# gismoviv1.net
KiCad netlist of a schematic drawn in EAGLE
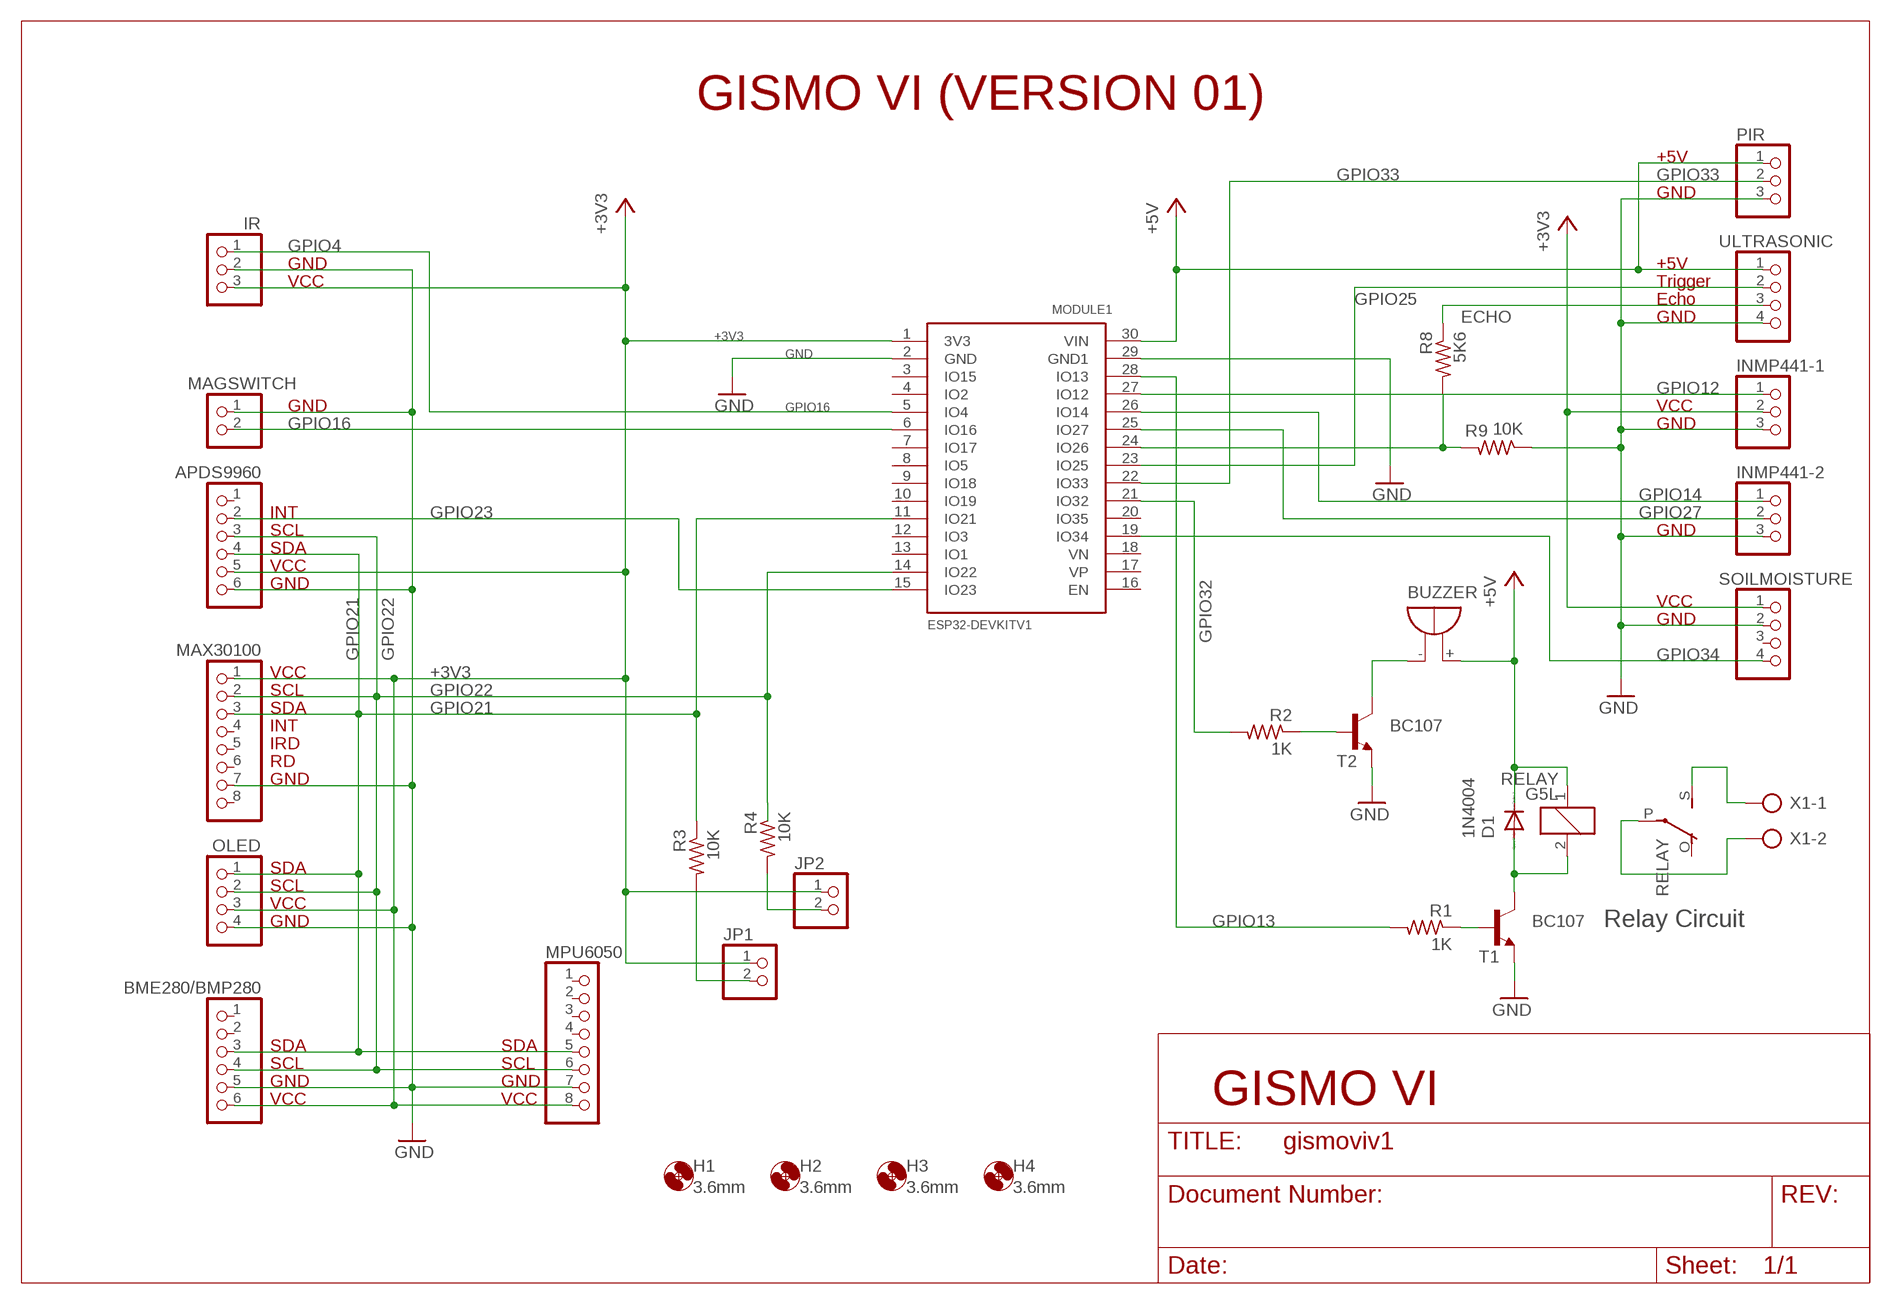
[diagram p0: schematic, sheet 1]

(export (version "E")
  (design (tool "Eeschema 10.0.6"))
  (components
    (comp (ref "APDS9960")
      (value "PINHD-1X6")
      (footprint "eagle-import:1X06")
      (libsource (lib "eagle-import") (part "PINHD-1X6"))
    )
    (comp (ref "BME280/BMP280")
      (value "PINHD-1X6")
      (footprint "eagle-import:1X06")
      (libsource (lib "eagle-import") (part "PINHD-1X6"))
    )
    (comp (ref "BUZZER")
      (value "F/QMB")
      (footprint "eagle-import:F_QMB")
      (libsource (lib "eagle-import") (part "F/QMB"))
    )
    (comp (ref "D1")
      (value "1N4004")
      (footprint "eagle-import:DO41-10")
      (libsource (lib "eagle-import") (part "1N4004"))
    )
    (comp (ref "H1")
      (value "3.6mm")
      (footprint "eagle-import:3,6")
      (libsource (lib "eagle-import") (part "MOUNT-HOLE3.6"))
    )
    (comp (ref "H2")
      (value "3.6mm")
      (footprint "eagle-import:3,6")
      (libsource (lib "eagle-import") (part "MOUNT-HOLE3.6"))
    )
    (comp (ref "H3")
      (value "3.6mm")
      (footprint "eagle-import:3,6")
      (libsource (lib "eagle-import") (part "MOUNT-HOLE3.6"))
    )
    (comp (ref "H4")
      (value "3.6mm")
      (footprint "eagle-import:3,6")
      (libsource (lib "eagle-import") (part "MOUNT-HOLE3.6"))
    )
    (comp (ref "INMP441-1")
      (value "PINHD-1X3")
      (footprint "eagle-import:1X03")
      (libsource (lib "eagle-import") (part "PINHD-1X3"))
    )
    (comp (ref "INMP441-2")
      (value "PINHD-1X3")
      (footprint "eagle-import:1X03")
      (libsource (lib "eagle-import") (part "PINHD-1X3"))
    )
    (comp (ref "IR")
      (value "PINHD-1X3")
      (footprint "eagle-import:1X03")
      (libsource (lib "eagle-import") (part "PINHD-1X3"))
    )
    (comp (ref "JP1")
      (value "PINHD-1X2")
      (footprint "eagle-import:1X02")
      (libsource (lib "eagle-import") (part "PINHD-1X2"))
    )
    (comp (ref "JP2")
      (value "PINHD-1X2")
      (footprint "eagle-import:1X02")
      (libsource (lib "eagle-import") (part "PINHD-1X2"))
    )
    (comp (ref "MAGSWITCH")
      (value "PINHD-1X2")
      (footprint "eagle-import:1X02")
      (libsource (lib "eagle-import") (part "PINHD-1X2"))
    )
    (comp (ref "MAX30100")
      (value "PINHD-1X8")
      (footprint "eagle-import:1X08")
      (libsource (lib "eagle-import") (part "PINHD-1X8"))
    )
    (comp (ref "MODULE1")
      (value "ESP32DEVKITV1")
      (footprint "eagle-import:ESP32-DEVKITV1")
      (libsource (lib "eagle-import") (part "ESP32DEVKITV1"))
    )
    (comp (ref "MPU6050")
      (value "PINHD-1X8")
      (footprint "eagle-import:1X08")
      (libsource (lib "eagle-import") (part "PINHD-1X8"))
    )
    (comp (ref "OLED")
      (value "PINHD-1X4")
      (footprint "eagle-import:1X04")
      (libsource (lib "eagle-import") (part "PINHD-1X4"))
    )
    (comp (ref "PIR")
      (value "PINHD-1X3")
      (footprint "eagle-import:1X03")
      (libsource (lib "eagle-import") (part "PINHD-1X3"))
    )
    (comp (ref "R1")
      (value "1K")
      (footprint "eagle-import:0204_7")
      (libsource (lib "eagle-import") (part "R-US_0204/7"))
    )
    (comp (ref "R2")
      (value "1K")
      (footprint "eagle-import:0204_7")
      (libsource (lib "eagle-import") (part "R-US_0204/7"))
    )
    (comp (ref "R3")
      (value "10K")
      (footprint "eagle-import:0204_7")
      (libsource (lib "eagle-import") (part "R-US_0204/7"))
    )
    (comp (ref "R4")
      (value "10K")
      (footprint "eagle-import:0204_7")
      (libsource (lib "eagle-import") (part "R-US_0204/7"))
    )
    (comp (ref "R8")
      (value "5K6")
      (footprint "eagle-import:0204_7")
      (libsource (lib "eagle-import") (part "R-US_0204/7"))
    )
    (comp (ref "R9")
      (value "10K")
      (footprint "eagle-import:0204_7")
      (libsource (lib "eagle-import") (part "R-US_0204/7"))
    )
    (comp (ref "RELAY")
      (value "G5L")
      (footprint "eagle-import:G5LE")
      (libsource (lib "eagle-import") (part "G5L"))
    )
    (comp (ref "SOILMOISTURE")
      (value "PINHD-1X4")
      (footprint "eagle-import:1X04")
      (libsource (lib "eagle-import") (part "PINHD-1X4"))
    )
    (comp (ref "T1")
      (value "BC107")
      (footprint "eagle-import:TO18")
      (libsource (lib "eagle-import") (part "-NPN-TO18-EBCBC107A"))
    )
    (comp (ref "T2")
      (value "BC107")
      (footprint "eagle-import:TO18")
      (libsource (lib "eagle-import") (part "-NPN-TO18-EBCBC107A"))
    )
    (comp (ref "ULTRASONIC")
      (value "PINHD-1X4")
      (footprint "eagle-import:1X04")
      (libsource (lib "eagle-import") (part "PINHD-1X4"))
    )
    (comp (ref "X1")
      (value "AK500/2")
      (footprint "eagle-import:AK500_2")
      (libsource (lib "eagle-import") (part "AK500/2"))
    )
  )
  (nets
    (net (code "1") (name "+3V3") (class "Default")
      (node (ref "APDS9960") (pin "5") (pinfunction "5_5") (pintype "passive"))
      (node (ref "BME280/BMP280") (pin "6") (pinfunction "6_6") (pintype "passive"))
      (node (ref "INMP441-1") (pin "2") (pinfunction "2_2") (pintype "passive"))
      (node (ref "IR") (pin "3") (pinfunction "3_3") (pintype "passive"))
      (node (ref "JP1") (pin "1") (pinfunction "1_1") (pintype "passive"))
      (node (ref "JP2") (pin "1") (pinfunction "1_1") (pintype "passive"))
      (node (ref "MAX30100") (pin "1") (pinfunction "1_1") (pintype "passive"))
      (node (ref "MODULE1") (pin "1") (pinfunction "3V3_1") (pintype "bidirectional"))
      (node (ref "MPU6050") (pin "8") (pinfunction "8_8") (pintype "passive"))
      (node (ref "OLED") (pin "3") (pinfunction "3_3") (pintype "passive"))
      (node (ref "SOILMOISTURE") (pin "1") (pinfunction "1_1") (pintype "passive"))
    )
    (net (code "2") (name "+5V") (class "Default")
      (node (ref "BUZZER") (pin "+") (pinfunction "-_+") (pintype "passive"))
      (node (ref "D1") (pin "C") (pinfunction "C_C") (pintype "passive"))
      (node (ref "MODULE1") (pin "30") (pinfunction "VIN_30") (pintype "bidirectional"))
      (node (ref "PIR") (pin "1") (pinfunction "1_1") (pintype "passive"))
      (node (ref "RELAY") (pin "1") (pinfunction "1_1") (pintype "passive"))
      (node (ref "ULTRASONIC") (pin "1") (pinfunction "1_1") (pintype "passive"))
    )
    (net (code "3") (name "/ECHO") (class "Default")
      (node (ref "R8") (pin "1") (pinfunction "1_1") (pintype "passive"))
      (node (ref "ULTRASONIC") (pin "3") (pinfunction "3_3") (pintype "passive"))
    )
    (net (code "4") (name "/GPIO4") (class "Default")
      (node (ref "IR") (pin "1") (pinfunction "1_1") (pintype "passive"))
      (node (ref "MODULE1") (pin "5") (pinfunction "IO4_5") (pintype "bidirectional"))
    )
    (net (code "5") (name "/GPIO12") (class "Default")
      (node (ref "INMP441-1") (pin "1") (pinfunction "1_1") (pintype "passive"))
      (node (ref "MODULE1") (pin "27") (pinfunction "IO12_27") (pintype "bidirectional"))
    )
    (net (code "6") (name "/GPIO13") (class "Default")
      (node (ref "MODULE1") (pin "28") (pinfunction "IO13_28") (pintype "bidirectional"))
      (node (ref "R1") (pin "2") (pinfunction "2_2") (pintype "passive"))
    )
    (net (code "7") (name "/GPIO14") (class "Default")
      (node (ref "INMP441-2") (pin "1") (pinfunction "1_1") (pintype "passive"))
      (node (ref "MODULE1") (pin "26") (pinfunction "IO14_26") (pintype "bidirectional"))
    )
    (net (code "8") (name "/GPIO16") (class "Default")
      (node (ref "MAGSWITCH") (pin "2") (pinfunction "2_2") (pintype "passive"))
      (node (ref "MODULE1") (pin "6") (pinfunction "IO16_6") (pintype "bidirectional"))
    )
    (net (code "9") (name "/GPIO21") (class "Default")
      (node (ref "APDS9960") (pin "4") (pinfunction "4_4") (pintype "passive"))
      (node (ref "BME280/BMP280") (pin "3") (pinfunction "3_3") (pintype "passive"))
      (node (ref "MAX30100") (pin "3") (pinfunction "3_3") (pintype "passive"))
      (node (ref "MODULE1") (pin "11") (pinfunction "IO21_11") (pintype "bidirectional"))
      (node (ref "MPU6050") (pin "5") (pinfunction "5_5") (pintype "passive"))
      (node (ref "OLED") (pin "1") (pinfunction "1_1") (pintype "passive"))
      (node (ref "R3") (pin "1") (pinfunction "1_1") (pintype "passive"))
    )
    (net (code "10") (name "/GPIO22") (class "Default")
      (node (ref "APDS9960") (pin "3") (pinfunction "3_3") (pintype "passive"))
      (node (ref "BME280/BMP280") (pin "4") (pinfunction "4_4") (pintype "passive"))
      (node (ref "MAX30100") (pin "2") (pinfunction "2_2") (pintype "passive"))
      (node (ref "MODULE1") (pin "14") (pinfunction "IO22_14") (pintype "bidirectional"))
      (node (ref "MPU6050") (pin "6") (pinfunction "6_6") (pintype "passive"))
      (node (ref "OLED") (pin "2") (pinfunction "2_2") (pintype "passive"))
      (node (ref "R4") (pin "1") (pinfunction "1_1") (pintype "passive"))
    )
    (net (code "11") (name "/GPIO23") (class "Default")
      (node (ref "APDS9960") (pin "2") (pinfunction "2_2") (pintype "passive"))
      (node (ref "MODULE1") (pin "15") (pinfunction "IO23_15") (pintype "bidirectional"))
    )
    (net (code "12") (name "/GPIO25") (class "Default")
      (node (ref "MODULE1") (pin "23") (pinfunction "IO25_23") (pintype "bidirectional"))
      (node (ref "ULTRASONIC") (pin "2") (pinfunction "2_2") (pintype "passive"))
    )
    (net (code "13") (name "/GPIO27") (class "Default")
      (node (ref "INMP441-2") (pin "2") (pinfunction "2_2") (pintype "passive"))
      (node (ref "MODULE1") (pin "25") (pinfunction "IO27_25") (pintype "bidirectional"))
    )
    (net (code "14") (name "/GPIO32") (class "Default")
      (node (ref "MODULE1") (pin "21") (pinfunction "IO32_21") (pintype "bidirectional"))
      (node (ref "R2") (pin "2") (pinfunction "2_2") (pintype "passive"))
    )
    (net (code "15") (name "/GPIO33") (class "Default")
      (node (ref "MODULE1") (pin "22") (pinfunction "IO33_22") (pintype "bidirectional"))
      (node (ref "PIR") (pin "2") (pinfunction "2_2") (pintype "passive"))
    )
    (net (code "16") (name "/GPIO34") (class "Default")
      (node (ref "MODULE1") (pin "19") (pinfunction "IO34_19") (pintype "bidirectional"))
      (node (ref "SOILMOISTURE") (pin "4") (pinfunction "4_4") (pintype "passive"))
    )
    (net (code "17") (name "GND") (class "Default")
      (node (ref "APDS9960") (pin "6") (pinfunction "6_6") (pintype "passive"))
      (node (ref "BME280/BMP280") (pin "5") (pinfunction "5_5") (pintype "passive"))
      (node (ref "INMP441-1") (pin "3") (pinfunction "3_3") (pintype "passive"))
      (node (ref "INMP441-2") (pin "3") (pinfunction "3_3") (pintype "passive"))
      (node (ref "IR") (pin "2") (pinfunction "2_2") (pintype "passive"))
      (node (ref "MAGSWITCH") (pin "1") (pinfunction "1_1") (pintype "passive"))
      (node (ref "MAX30100") (pin "7") (pinfunction "7_7") (pintype "passive"))
      (node (ref "MODULE1") (pin "2") (pinfunction "GND_2") (pintype "bidirectional"))
      (node (ref "MODULE1") (pin "29") (pinfunction "GND1_29") (pintype "bidirectional"))
      (node (ref "MPU6050") (pin "7") (pinfunction "7_7") (pintype "passive"))
      (node (ref "OLED") (pin "4") (pinfunction "4_4") (pintype "passive"))
      (node (ref "PIR") (pin "3") (pinfunction "3_3") (pintype "passive"))
      (node (ref "R9") (pin "1") (pinfunction "1_1") (pintype "passive"))
      (node (ref "SOILMOISTURE") (pin "2") (pinfunction "2_2") (pintype "passive"))
      (node (ref "T1") (pin "1") (pinfunction "E_1") (pintype "passive"))
      (node (ref "T2") (pin "1") (pinfunction "E_1") (pintype "passive"))
      (node (ref "ULTRASONIC") (pin "4") (pinfunction "4_4") (pintype "passive"))
    )
    (net (code "18") (name "Net-(BUZZER-+)") (class "Default")
      (node (ref "BUZZER") (pin "-") (pinfunction "+_-") (pintype "passive"))
      (node (ref "T2") (pin "3") (pinfunction "C_3") (pintype "passive"))
    )
    (net (code "19") (name "Net-(JP1-Pad2)") (class "Default")
      (node (ref "JP1") (pin "2") (pinfunction "2_2") (pintype "passive"))
      (node (ref "R3") (pin "2") (pinfunction "2_2") (pintype "passive"))
    )
    (net (code "20") (name "Net-(JP2-Pad2)") (class "Default")
      (node (ref "JP2") (pin "2") (pinfunction "2_2") (pintype "passive"))
      (node (ref "R4") (pin "2") (pinfunction "2_2") (pintype "passive"))
    )
    (net (code "21") (name "Net-(MODULE1-IO26)") (class "Default")
      (node (ref "MODULE1") (pin "24") (pinfunction "IO26_24") (pintype "bidirectional"))
      (node (ref "R8") (pin "2") (pinfunction "2_2") (pintype "passive"))
      (node (ref "R9") (pin "2") (pinfunction "2_2") (pintype "passive"))
    )
    (net (code "22") (name "Net-(T1-B)") (class "Default")
      (node (ref "R1") (pin "1") (pinfunction "1_1") (pintype "passive"))
      (node (ref "T1") (pin "2") (pinfunction "B_2") (pintype "passive"))
    )
    (net (code "23") (name "Net-(T1-C)") (class "Default")
      (node (ref "D1") (pin "A") (pinfunction "A_A") (pintype "passive"))
      (node (ref "RELAY") (pin "2") (pinfunction "2_2") (pintype "passive"))
      (node (ref "T1") (pin "3") (pinfunction "C_3") (pintype "passive"))
    )
    (net (code "24") (name "Net-(T2-B)") (class "Default")
      (node (ref "R2") (pin "1") (pinfunction "1_1") (pintype "passive"))
      (node (ref "T2") (pin "2") (pinfunction "B_2") (pintype "passive"))
    )
    (net (code "25") (name "Net-(X1A-KL)") (class "Default")
      (node (ref "RELAY") (pin "S") (pinfunction "S_S") (pintype "passive"))
      (node (ref "X1") (pin "1") (pinfunction "KL_1") (pintype "passive"))
    )
    (net (code "26") (name "Net-(X1B-KL)") (class "Default")
      (node (ref "RELAY") (pin "P") (pinfunction "P_P") (pintype "passive"))
      (node (ref "X1") (pin "2") (pinfunction "KL_2") (pintype "passive"))
    )
    (net (code "27") (name "unconnected-(APDS9960-Pad1)") (class "Default")
      (node (ref "APDS9960") (pin "1") (pinfunction "1_1") (pintype "passive"))
    )
    (net (code "28") (name "unconnected-(BME280/BMP280-Pad1)") (class "Default")
      (node (ref "BME280/BMP280") (pin "1") (pinfunction "1_1") (pintype "passive"))
    )
    (net (code "29") (name "unconnected-(BME280/BMP280-Pad2)") (class "Default")
      (node (ref "BME280/BMP280") (pin "2") (pinfunction "2_2") (pintype "passive"))
    )
    (net (code "30") (name "unconnected-(MAX30100-Pad4)") (class "Default")
      (node (ref "MAX30100") (pin "4") (pinfunction "4_4") (pintype "passive"))
    )
    (net (code "31") (name "unconnected-(MAX30100-Pad5)") (class "Default")
      (node (ref "MAX30100") (pin "5") (pinfunction "5_5") (pintype "passive"))
    )
    (net (code "32") (name "unconnected-(MAX30100-Pad6)") (class "Default")
      (node (ref "MAX30100") (pin "6") (pinfunction "6_6") (pintype "passive"))
    )
    (net (code "33") (name "unconnected-(MAX30100-Pad8)") (class "Default")
      (node (ref "MAX30100") (pin "8") (pinfunction "8_8") (pintype "passive"))
    )
    (net (code "34") (name "unconnected-(MODULE1-EN-Pad16)") (class "Default")
      (node (ref "MODULE1") (pin "16") (pinfunction "EN_16") (pintype "bidirectional"))
    )
    (net (code "35") (name "unconnected-(MODULE1-IO1-Pad13)") (class "Default")
      (node (ref "MODULE1") (pin "13") (pinfunction "IO1_13") (pintype "bidirectional"))
    )
    (net (code "36") (name "unconnected-(MODULE1-IO2-Pad4)") (class "Default")
      (node (ref "MODULE1") (pin "4") (pinfunction "IO2_4") (pintype "bidirectional"))
    )
    (net (code "37") (name "unconnected-(MODULE1-IO3-Pad12)") (class "Default")
      (node (ref "MODULE1") (pin "12") (pinfunction "IO3_12") (pintype "bidirectional"))
    )
    (net (code "38") (name "unconnected-(MODULE1-IO5-Pad8)") (class "Default")
      (node (ref "MODULE1") (pin "8") (pinfunction "IO5_8") (pintype "bidirectional"))
    )
    (net (code "39") (name "unconnected-(MODULE1-IO15-Pad3)") (class "Default")
      (node (ref "MODULE1") (pin "3") (pinfunction "IO15_3") (pintype "bidirectional"))
    )
    (net (code "40") (name "unconnected-(MODULE1-IO17-Pad7)") (class "Default")
      (node (ref "MODULE1") (pin "7") (pinfunction "IO17_7") (pintype "bidirectional"))
    )
    (net (code "41") (name "unconnected-(MODULE1-IO18-Pad9)") (class "Default")
      (node (ref "MODULE1") (pin "9") (pinfunction "IO18_9") (pintype "bidirectional"))
    )
    (net (code "42") (name "unconnected-(MODULE1-IO19-Pad10)") (class "Default")
      (node (ref "MODULE1") (pin "10") (pinfunction "IO19_10") (pintype "bidirectional"))
    )
    (net (code "43") (name "unconnected-(MODULE1-IO35-Pad20)") (class "Default")
      (node (ref "MODULE1") (pin "20") (pinfunction "IO35_20") (pintype "bidirectional"))
    )
    (net (code "44") (name "unconnected-(MODULE1-VN-Pad18)") (class "Default")
      (node (ref "MODULE1") (pin "18") (pinfunction "VN_18") (pintype "bidirectional"))
    )
    (net (code "45") (name "unconnected-(MODULE1-VP-Pad17)") (class "Default")
      (node (ref "MODULE1") (pin "17") (pinfunction "VP_17") (pintype "bidirectional"))
    )
    (net (code "46") (name "unconnected-(MPU6050-Pad1)") (class "Default")
      (node (ref "MPU6050") (pin "1") (pinfunction "1_1") (pintype "passive"))
    )
    (net (code "47") (name "unconnected-(MPU6050-Pad2)") (class "Default")
      (node (ref "MPU6050") (pin "2") (pinfunction "2_2") (pintype "passive"))
    )
    (net (code "48") (name "unconnected-(MPU6050-Pad3)") (class "Default")
      (node (ref "MPU6050") (pin "3") (pinfunction "3_3") (pintype "passive"))
    )
    (net (code "49") (name "unconnected-(MPU6050-Pad4)") (class "Default")
      (node (ref "MPU6050") (pin "4") (pinfunction "4_4") (pintype "passive"))
    )
    (net (code "50") (name "unconnected-(RELAY-PadO)") (class "Default")
      (node (ref "RELAY") (pin "O") (pinfunction "O_O") (pintype "passive"))
    )
    (net (code "51") (name "unconnected-(SOILMOISTURE-Pad3)") (class "Default")
      (node (ref "SOILMOISTURE") (pin "3") (pinfunction "3_3") (pintype "passive"))
    )
  )
)
